# Gumstix.net
KiCad netlist of a schematic drawn in Altium Designer
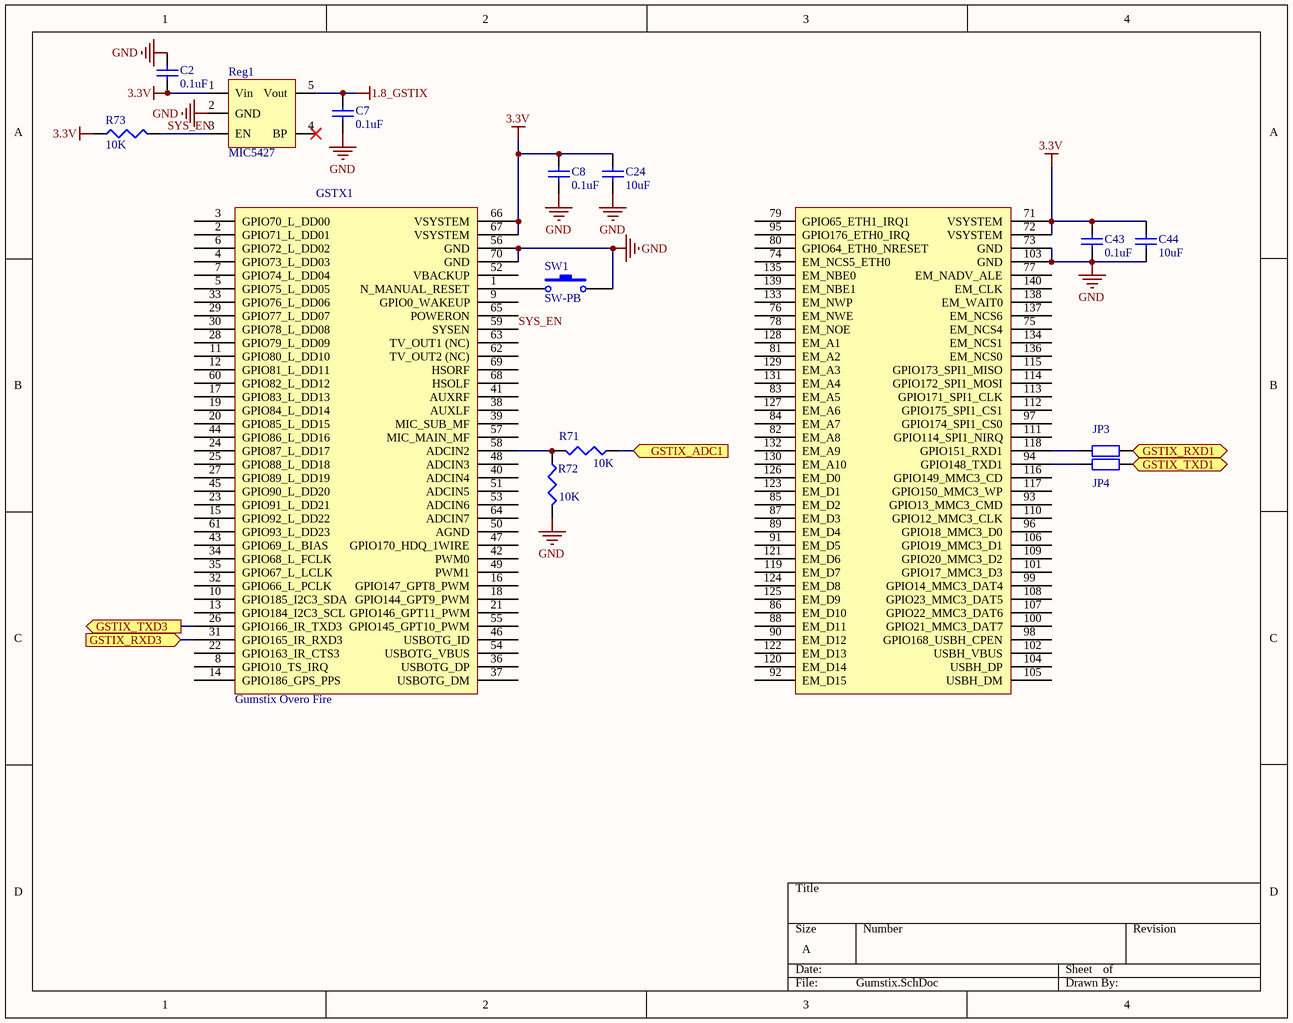
[diagram p0: Gumstix.SchDoc]

(export (version "E")
  (design (tool "Eeschema 10.0.6"))
  (components
    (comp (ref "C2")
      (value "0.1uF")
      (footprint "0603_CAP")
      (description "Capacitor")
      (fields (field (name "Comment") "X7R Cap") (field (name "PUBLISHER") "Altium Limited"))
      (libsource (lib "Miscellaneous Devices") (part "Cap"))
    )
    (comp (ref "C7")
      (value "0.1uF")
      (footprint "0603_CAP")
      (description "Capacitor")
      (fields (field (name "Comment") "X7R Cap") (field (name "PUBLISHER") "Altium Limited"))
      (libsource (lib "Miscellaneous Devices") (part "Cap"))
    )
    (comp (ref "C8")
      (value "0.1uF")
      (footprint "0603_CAP")
      (description "Capacitor")
      (fields (field (name "Comment") "X7R Cap") (field (name "PUBLISHER") "Altium Limited"))
      (libsource (lib "Miscellaneous Devices") (part "Cap"))
    )
    (comp (ref "C24")
      (value "10uF")
      (footprint "0603_CAP")
      (description "Capacitor")
      (fields (field (name "Comment") "X7R Cap") (field (name "PUBLISHER") "Altium Limited"))
      (libsource (lib "Miscellaneous Devices") (part "Cap"))
    )
    (comp (ref "C43")
      (value "0.1uF")
      (footprint "0603_CAP")
      (description "Capacitor")
      (fields (field (name "Comment") "X7R Cap") (field (name "PUBLISHER") "Altium Limited"))
      (libsource (lib "Miscellaneous Devices") (part "Cap"))
    )
    (comp (ref "C44")
      (value "10uF")
      (footprint "0603_CAP")
      (description "Capacitor")
      (fields (field (name "Comment") "X7R Cap") (field (name "PUBLISHER") "Altium Limited"))
      (libsource (lib "Miscellaneous Devices") (part "Cap"))
    )
    (comp (ref "GSTX1")
      (value "Gumstix Overo Fire")
      (footprint "GUMSTIX")
      (libsource (lib "Components") (part "GUMSTIX"))
    )
    (comp (ref "JP3")
      (value "~")
      (footprint "0603_RES")
      (description "Resistor")
      (fields (field (name "PUBLISHER") "Altium Limited"))
      (libsource (lib "Miscellaneous Devices") (part "Res2"))
    )
    (comp (ref "JP4")
      (value "~")
      (footprint "0603_RES")
      (description "Resistor")
      (fields (field (name "PUBLISHER") "Altium Limited"))
      (libsource (lib "Miscellaneous Devices") (part "Res2"))
    )
    (comp (ref "R71")
      (value "10K")
      (footprint "0603_RES")
      (description "Resistor")
      (fields (field (name "Comment") "Rpull") (field (name "PUBLISHER") "Altium Limited"))
      (libsource (lib "Miscellaneous Devices") (part "Res3"))
    )
    (comp (ref "R72")
      (value "10K")
      (footprint "0603_RES")
      (description "Resistor")
      (fields (field (name "Comment") "Rpull") (field (name "PUBLISHER") "Altium Limited"))
      (libsource (lib "Miscellaneous Devices") (part "Res3"))
    )
    (comp (ref "R73")
      (value "10K")
      (footprint "0603_RES")
      (description "Resistor")
      (fields (field (name "Comment") "Rpull") (field (name "PUBLISHER") "Altium Limited"))
      (libsource (lib "Miscellaneous Devices") (part "Res3"))
    )
    (comp (ref "Reg1")
      (value "MIC5427")
      (footprint "SOT23-STD-5-Lead")
      (description "576-1288-1-ND")
      (fields
        (field (name "MANUFACTURER") "Micrel Inc")
        (field (name "MANUFACTURER PART NUMBER") "MIC5247-1.8YM5 TR")
      )
      (libsource (lib "Components") (part "1.8V LDO Regulator"))
    )
    (comp (ref "SW1")
      (value "SW-PB")
      (footprint "SM_SW")
      (description "Switch")
      (fields
        (field (name "MANUFACTURER") "C&K Components")
        (field (name "MANUFACTURER PART NUMBER") "PTS525SK08SMTR LFS")
        (field (name "PUBLISHER") "Altium Limited")
      )
      (libsource (lib "Miscellaneous Devices") (part "SW-PB"))
    )
  )
  (nets
    (net (code "1") (name "/GSTIX_ADC1") (class "Default")
      (node (ref "R71") (pin "1") (pinfunction "1_1") (pintype "passive"))
    )
    (net (code "2") (name "/GSTIX_RXD1") (class "Default")
      (node (ref "JP3") (pin "2") (pinfunction "2_2") (pintype "passive"))
    )
    (net (code "3") (name "/GSTIX_RXD3") (class "Default")
      (node (ref "GSTX1") (pin "31") (pinfunction "GPIO165_IR_RXD3_31") (pintype "passive"))
    )
    (net (code "4") (name "/GSTIX_TXD1") (class "Default")
      (node (ref "JP4") (pin "2") (pinfunction "2_2") (pintype "passive"))
    )
    (net (code "5") (name "/GSTIX_TXD3") (class "Default")
      (node (ref "GSTX1") (pin "26") (pinfunction "GPIO166_IR_TXD3_26") (pintype "passive"))
    )
    (net (code "6") (name "/SYS_EN") (class "Default")
      (node (ref "GSTX1") (pin "59") (pinfunction "SYSEN_59") (pintype "passive"))
      (node (ref "R73") (pin "2") (pinfunction "2_2") (pintype "passive"))
      (node (ref "Reg1") (pin "3") (pinfunction "EN_3") (pintype "passive"))
    )
    (net (code "7") (name "1.8_GSTIX") (class "Default")
      (node (ref "C7") (pin "1") (pinfunction "1_1") (pintype "passive"))
      (node (ref "Reg1") (pin "5") (pinfunction "Vout_5") (pintype "passive"))
    )
    (net (code "8") (name "3.3V") (class "Default")
      (node (ref "C2") (pin "1") (pinfunction "1_1") (pintype "passive"))
      (node (ref "C24") (pin "1") (pinfunction "1_1") (pintype "passive"))
      (node (ref "C43") (pin "1") (pinfunction "1_1") (pintype "passive"))
      (node (ref "C44") (pin "1") (pinfunction "1_1") (pintype "passive"))
      (node (ref "C8") (pin "1") (pinfunction "1_1") (pintype "passive"))
      (node (ref "GSTX1") (pin "66") (pinfunction "VSYSTEM_66") (pintype "passive"))
      (node (ref "GSTX1") (pin "67") (pinfunction "VSYSTEM_67") (pintype "passive"))
      (node (ref "GSTX1") (pin "71") (pinfunction "VSYSTEM_71") (pintype "passive"))
      (node (ref "GSTX1") (pin "72") (pinfunction "VSYSTEM_72") (pintype "passive"))
      (node (ref "R73") (pin "1") (pinfunction "1_1") (pintype "passive"))
      (node (ref "Reg1") (pin "1") (pinfunction "Vin_1") (pintype "passive"))
    )
    (net (code "9") (name "GND") (class "Default")
      (node (ref "C2") (pin "2") (pinfunction "2_2") (pintype "passive"))
      (node (ref "C24") (pin "2") (pinfunction "2_2") (pintype "passive"))
      (node (ref "C43") (pin "2") (pinfunction "2_2") (pintype "passive"))
      (node (ref "C44") (pin "2") (pinfunction "2_2") (pintype "passive"))
      (node (ref "C7") (pin "2") (pinfunction "2_2") (pintype "passive"))
      (node (ref "C8") (pin "2") (pinfunction "2_2") (pintype "passive"))
      (node (ref "GSTX1") (pin "103") (pinfunction "GND_103") (pintype "passive"))
      (node (ref "GSTX1") (pin "56") (pinfunction "GND_56") (pintype "passive"))
      (node (ref "GSTX1") (pin "70") (pinfunction "GND_70") (pintype "passive"))
      (node (ref "GSTX1") (pin "73") (pinfunction "GND_73") (pintype "passive"))
      (node (ref "R72") (pin "2") (pinfunction "2_2") (pintype "passive"))
      (node (ref "Reg1") (pin "2") (pinfunction "GND_2") (pintype "passive"))
      (node (ref "SW1") (pin "2") (pinfunction "2_2") (pintype "passive"))
    )
    (net (code "10") (name "Net-(GSTX1-ADCIN2)") (class "Default")
      (node (ref "GSTX1") (pin "58") (pinfunction "ADCIN2_58") (pintype "passive"))
      (node (ref "R71") (pin "2") (pinfunction "2_2") (pintype "passive"))
      (node (ref "R72") (pin "1") (pinfunction "1_1") (pintype "passive"))
    )
    (net (code "11") (name "Net-(GSTX1-GPIO148_TXD1)") (class "Default")
      (node (ref "GSTX1") (pin "94") (pinfunction "GPIO148_TXD1_94") (pintype "passive"))
      (node (ref "JP4") (pin "1") (pinfunction "1_1") (pintype "passive"))
    )
    (net (code "12") (name "Net-(GSTX1-GPIO151_RXD1)") (class "Default")
      (node (ref "GSTX1") (pin "118") (pinfunction "GPIO151_RXD1_118") (pintype "passive"))
      (node (ref "JP3") (pin "1") (pinfunction "1_1") (pintype "passive"))
    )
    (net (code "13") (name "Net-(GSTX1-N_MANUAL_RESET)") (class "Default")
      (node (ref "GSTX1") (pin "1") (pinfunction "N_MANUAL_RESET_1") (pintype "passive"))
      (node (ref "SW1") (pin "1") (pinfunction "1_1") (pintype "passive"))
    )
    (net (code "14") (name "unconnected-(GSTX1-ADCIN3-Pad48)") (class "Default")
      (node (ref "GSTX1") (pin "48") (pinfunction "ADCIN3_48") (pintype "passive"))
    )
    (net (code "15") (name "unconnected-(GSTX1-ADCIN4-Pad40)") (class "Default")
      (node (ref "GSTX1") (pin "40") (pinfunction "ADCIN4_40") (pintype "passive"))
    )
    (net (code "16") (name "unconnected-(GSTX1-ADCIN5-Pad51)") (class "Default")
      (node (ref "GSTX1") (pin "51") (pinfunction "ADCIN5_51") (pintype "passive"))
    )
    (net (code "17") (name "unconnected-(GSTX1-ADCIN6-Pad53)") (class "Default")
      (node (ref "GSTX1") (pin "53") (pinfunction "ADCIN6_53") (pintype "passive"))
    )
    (net (code "18") (name "unconnected-(GSTX1-ADCIN7-Pad64)") (class "Default")
      (node (ref "GSTX1") (pin "64") (pinfunction "ADCIN7_64") (pintype "passive"))
    )
    (net (code "19") (name "unconnected-(GSTX1-AGND-Pad50)") (class "Default")
      (node (ref "GSTX1") (pin "50") (pinfunction "AGND_50") (pintype "passive"))
    )
    (net (code "20") (name "unconnected-(GSTX1-AUXLF-Pad38)") (class "Default")
      (node (ref "GSTX1") (pin "38") (pinfunction "AUXLF_38") (pintype "passive"))
    )
    (net (code "21") (name "unconnected-(GSTX1-AUXRF-Pad41)") (class "Default")
      (node (ref "GSTX1") (pin "41") (pinfunction "AUXRF_41") (pintype "passive"))
    )
    (net (code "22") (name "unconnected-(GSTX1-EM_A1-Pad128)") (class "Default")
      (node (ref "GSTX1") (pin "128") (pinfunction "EM_A1_128") (pintype "passive"))
    )
    (net (code "23") (name "unconnected-(GSTX1-EM_A2-Pad81)") (class "Default")
      (node (ref "GSTX1") (pin "81") (pinfunction "EM_A2_81") (pintype "passive"))
    )
    (net (code "24") (name "unconnected-(GSTX1-EM_A3-Pad129)") (class "Default")
      (node (ref "GSTX1") (pin "129") (pinfunction "EM_A3_129") (pintype "passive"))
    )
    (net (code "25") (name "unconnected-(GSTX1-EM_A4-Pad131)") (class "Default")
      (node (ref "GSTX1") (pin "131") (pinfunction "EM_A4_131") (pintype "passive"))
    )
    (net (code "26") (name "unconnected-(GSTX1-EM_A5-Pad83)") (class "Default")
      (node (ref "GSTX1") (pin "83") (pinfunction "EM_A5_83") (pintype "passive"))
    )
    (net (code "27") (name "unconnected-(GSTX1-EM_A6-Pad127)") (class "Default")
      (node (ref "GSTX1") (pin "127") (pinfunction "EM_A6_127") (pintype "passive"))
    )
    (net (code "28") (name "unconnected-(GSTX1-EM_A7-Pad84)") (class "Default")
      (node (ref "GSTX1") (pin "84") (pinfunction "EM_A7_84") (pintype "passive"))
    )
    (net (code "29") (name "unconnected-(GSTX1-EM_A8-Pad82)") (class "Default")
      (node (ref "GSTX1") (pin "82") (pinfunction "EM_A8_82") (pintype "passive"))
    )
    (net (code "30") (name "unconnected-(GSTX1-EM_A9-Pad132)") (class "Default")
      (node (ref "GSTX1") (pin "132") (pinfunction "EM_A9_132") (pintype "passive"))
    )
    (net (code "31") (name "unconnected-(GSTX1-EM_A10-Pad130)") (class "Default")
      (node (ref "GSTX1") (pin "130") (pinfunction "EM_A10_130") (pintype "passive"))
    )
    (net (code "32") (name "unconnected-(GSTX1-EM_CLK-Pad140)") (class "Default")
      (node (ref "GSTX1") (pin "140") (pinfunction "EM_CLK_140") (pintype "passive"))
    )
    (net (code "33") (name "unconnected-(GSTX1-EM_D0-Pad126)") (class "Default")
      (node (ref "GSTX1") (pin "126") (pinfunction "EM_D0_126") (pintype "passive"))
    )
    (net (code "34") (name "unconnected-(GSTX1-EM_D1-Pad123)") (class "Default")
      (node (ref "GSTX1") (pin "123") (pinfunction "EM_D1_123") (pintype "passive"))
    )
    (net (code "35") (name "unconnected-(GSTX1-EM_D2-Pad85)") (class "Default")
      (node (ref "GSTX1") (pin "85") (pinfunction "EM_D2_85") (pintype "passive"))
    )
    (net (code "36") (name "unconnected-(GSTX1-EM_D3-Pad87)") (class "Default")
      (node (ref "GSTX1") (pin "87") (pinfunction "EM_D3_87") (pintype "passive"))
    )
    (net (code "37") (name "unconnected-(GSTX1-EM_D4-Pad89)") (class "Default")
      (node (ref "GSTX1") (pin "89") (pinfunction "EM_D4_89") (pintype "passive"))
    )
    (net (code "38") (name "unconnected-(GSTX1-EM_D5-Pad91)") (class "Default")
      (node (ref "GSTX1") (pin "91") (pinfunction "EM_D5_91") (pintype "passive"))
    )
    (net (code "39") (name "unconnected-(GSTX1-EM_D6-Pad121)") (class "Default")
      (node (ref "GSTX1") (pin "121") (pinfunction "EM_D6_121") (pintype "passive"))
    )
    (net (code "40") (name "unconnected-(GSTX1-EM_D7-Pad119)") (class "Default")
      (node (ref "GSTX1") (pin "119") (pinfunction "EM_D7_119") (pintype "passive"))
    )
    (net (code "41") (name "unconnected-(GSTX1-EM_D8-Pad124)") (class "Default")
      (node (ref "GSTX1") (pin "124") (pinfunction "EM_D8_124") (pintype "passive"))
    )
    (net (code "42") (name "unconnected-(GSTX1-EM_D9-Pad125)") (class "Default")
      (node (ref "GSTX1") (pin "125") (pinfunction "EM_D9_125") (pintype "passive"))
    )
    (net (code "43") (name "unconnected-(GSTX1-EM_D10-Pad86)") (class "Default")
      (node (ref "GSTX1") (pin "86") (pinfunction "EM_D10_86") (pintype "passive"))
    )
    (net (code "44") (name "unconnected-(GSTX1-EM_D11-Pad88)") (class "Default")
      (node (ref "GSTX1") (pin "88") (pinfunction "EM_D11_88") (pintype "passive"))
    )
    (net (code "45") (name "unconnected-(GSTX1-EM_D12-Pad90)") (class "Default")
      (node (ref "GSTX1") (pin "90") (pinfunction "EM_D12_90") (pintype "passive"))
    )
    (net (code "46") (name "unconnected-(GSTX1-EM_D13-Pad122)") (class "Default")
      (node (ref "GSTX1") (pin "122") (pinfunction "EM_D13_122") (pintype "passive"))
    )
    (net (code "47") (name "unconnected-(GSTX1-EM_D14-Pad120)") (class "Default")
      (node (ref "GSTX1") (pin "120") (pinfunction "EM_D14_120") (pintype "passive"))
    )
    (net (code "48") (name "unconnected-(GSTX1-EM_D15-Pad92)") (class "Default")
      (node (ref "GSTX1") (pin "92") (pinfunction "EM_D15_92") (pintype "passive"))
    )
    (net (code "49") (name "unconnected-(GSTX1-EM_NADV_ALE-Pad77)") (class "Default")
      (node (ref "GSTX1") (pin "77") (pinfunction "EM_NADV_ALE_77") (pintype "passive"))
    )
    (net (code "50") (name "unconnected-(GSTX1-EM_NBE0-Pad135)") (class "Default")
      (node (ref "GSTX1") (pin "135") (pinfunction "EM_NBE0_135") (pintype "passive"))
    )
    (net (code "51") (name "unconnected-(GSTX1-EM_NBE1-Pad139)") (class "Default")
      (node (ref "GSTX1") (pin "139") (pinfunction "EM_NBE1_139") (pintype "passive"))
    )
    (net (code "52") (name "unconnected-(GSTX1-EM_NCS0-Pad136)") (class "Default")
      (node (ref "GSTX1") (pin "136") (pinfunction "EM_NCS0_136") (pintype "passive"))
    )
    (net (code "53") (name "unconnected-(GSTX1-EM_NCS1-Pad134)") (class "Default")
      (node (ref "GSTX1") (pin "134") (pinfunction "EM_NCS1_134") (pintype "passive"))
    )
    (net (code "54") (name "unconnected-(GSTX1-EM_NCS4-Pad75)") (class "Default")
      (node (ref "GSTX1") (pin "75") (pinfunction "EM_NCS4_75") (pintype "passive"))
    )
    (net (code "55") (name "unconnected-(GSTX1-EM_NCS5_ETH0-Pad74)") (class "Default")
      (node (ref "GSTX1") (pin "74") (pinfunction "EM_NCS5_ETH0_74") (pintype "passive"))
    )
    (net (code "56") (name "unconnected-(GSTX1-EM_NCS6-Pad137)") (class "Default")
      (node (ref "GSTX1") (pin "137") (pinfunction "EM_NCS6_137") (pintype "passive"))
    )
    (net (code "57") (name "unconnected-(GSTX1-EM_NOE-Pad78)") (class "Default")
      (node (ref "GSTX1") (pin "78") (pinfunction "EM_NOE_78") (pintype "passive"))
    )
    (net (code "58") (name "unconnected-(GSTX1-EM_NWE-Pad76)") (class "Default")
      (node (ref "GSTX1") (pin "76") (pinfunction "EM_NWE_76") (pintype "passive"))
    )
    (net (code "59") (name "unconnected-(GSTX1-EM_NWP-Pad133)") (class "Default")
      (node (ref "GSTX1") (pin "133") (pinfunction "EM_NWP_133") (pintype "passive"))
    )
    (net (code "60") (name "unconnected-(GSTX1-EM_WAIT0-Pad138)") (class "Default")
      (node (ref "GSTX1") (pin "138") (pinfunction "EM_WAIT0_138") (pintype "passive"))
    )
    (net (code "61") (name "unconnected-(GSTX1-GPIO0_WAKEUP-Pad9)") (class "Default")
      (node (ref "GSTX1") (pin "9") (pinfunction "GPIO0_WAKEUP_9") (pintype "passive"))
    )
    (net (code "62") (name "unconnected-(GSTX1-GPIO10_TS_IRQ-Pad8)") (class "Default")
      (node (ref "GSTX1") (pin "8") (pinfunction "GPIO10_TS_IRQ_8") (pintype "passive"))
    )
    (net (code "63") (name "unconnected-(GSTX1-GPIO12_MMC3_CLK-Pad110)") (class "Default")
      (node (ref "GSTX1") (pin "110") (pinfunction "GPIO12_MMC3_CLK_110") (pintype "passive"))
    )
    (net (code "64") (name "unconnected-(GSTX1-GPIO13_MMC3_CMD-Pad93)") (class "Default")
      (node (ref "GSTX1") (pin "93") (pinfunction "GPIO13_MMC3_CMD_93") (pintype "passive"))
    )
    (net (code "65") (name "unconnected-(GSTX1-GPIO14_MMC3_DAT4-Pad99)") (class "Default")
      (node (ref "GSTX1") (pin "99") (pinfunction "GPIO14_MMC3_DAT4_99") (pintype "passive"))
    )
    (net (code "66") (name "unconnected-(GSTX1-GPIO17_MMC3_D3-Pad101)") (class "Default")
      (node (ref "GSTX1") (pin "101") (pinfunction "GPIO17_MMC3_D3_101") (pintype "passive"))
    )
    (net (code "67") (name "unconnected-(GSTX1-GPIO18_MMC3_D0-Pad96)") (class "Default")
      (node (ref "GSTX1") (pin "96") (pinfunction "GPIO18_MMC3_D0_96") (pintype "passive"))
    )
    (net (code "68") (name "unconnected-(GSTX1-GPIO19_MMC3_D1-Pad106)") (class "Default")
      (node (ref "GSTX1") (pin "106") (pinfunction "GPIO19_MMC3_D1_106") (pintype "passive"))
    )
    (net (code "69") (name "unconnected-(GSTX1-GPIO20_MMC3_D2-Pad109)") (class "Default")
      (node (ref "GSTX1") (pin "109") (pinfunction "GPIO20_MMC3_D2_109") (pintype "passive"))
    )
    (net (code "70") (name "unconnected-(GSTX1-GPIO21_MMC3_DAT7-Pad100)") (class "Default")
      (node (ref "GSTX1") (pin "100") (pinfunction "GPIO21_MMC3_DAT7_100") (pintype "passive"))
    )
    (net (code "71") (name "unconnected-(GSTX1-GPIO22_MMC3_DAT6-Pad107)") (class "Default")
      (node (ref "GSTX1") (pin "107") (pinfunction "GPIO22_MMC3_DAT6_107") (pintype "passive"))
    )
    (net (code "72") (name "unconnected-(GSTX1-GPIO23_MMC3_DAT5-Pad108)") (class "Default")
      (node (ref "GSTX1") (pin "108") (pinfunction "GPIO23_MMC3_DAT5_108") (pintype "passive"))
    )
    (net (code "73") (name "unconnected-(GSTX1-GPIO64_ETH0_NRESET-Pad80)") (class "Default")
      (node (ref "GSTX1") (pin "80") (pinfunction "GPIO64_ETH0_NRESET_80") (pintype "passive"))
    )
    (net (code "74") (name "unconnected-(GSTX1-GPIO65_ETH1_IRQ1-Pad79)") (class "Default")
      (node (ref "GSTX1") (pin "79") (pinfunction "GPIO65_ETH1_IRQ1_79") (pintype "passive"))
    )
    (net (code "75") (name "unconnected-(GSTX1-GPIO66_L_PCLK-Pad32)") (class "Default")
      (node (ref "GSTX1") (pin "32") (pinfunction "GPIO66_L_PCLK_32") (pintype "passive"))
    )
    (net (code "76") (name "unconnected-(GSTX1-GPIO67_L_LCLK-Pad35)") (class "Default")
      (node (ref "GSTX1") (pin "35") (pinfunction "GPIO67_L_LCLK_35") (pintype "passive"))
    )
    (net (code "77") (name "unconnected-(GSTX1-GPIO68_L_FCLK-Pad34)") (class "Default")
      (node (ref "GSTX1") (pin "34") (pinfunction "GPIO68_L_FCLK_34") (pintype "passive"))
    )
    (net (code "78") (name "unconnected-(GSTX1-GPIO69_L_BIAS-Pad43)") (class "Default")
      (node (ref "GSTX1") (pin "43") (pinfunction "GPIO69_L_BIAS_43") (pintype "passive"))
    )
    (net (code "79") (name "unconnected-(GSTX1-GPIO70_L_DD00-Pad3)") (class "Default")
      (node (ref "GSTX1") (pin "3") (pinfunction "GPIO70_L_DD00_3") (pintype "passive"))
    )
    (net (code "80") (name "unconnected-(GSTX1-GPIO71_L_DD01-Pad2)") (class "Default")
      (node (ref "GSTX1") (pin "2") (pinfunction "GPIO71_L_DD01_2") (pintype "passive"))
    )
    (net (code "81") (name "unconnected-(GSTX1-GPIO72_L_DD02-Pad6)") (class "Default")
      (node (ref "GSTX1") (pin "6") (pinfunction "GPIO72_L_DD02_6") (pintype "passive"))
    )
    (net (code "82") (name "unconnected-(GSTX1-GPIO73_L_DD03-Pad4)") (class "Default")
      (node (ref "GSTX1") (pin "4") (pinfunction "GPIO73_L_DD03_4") (pintype "passive"))
    )
    (net (code "83") (name "unconnected-(GSTX1-GPIO74_L_DD04-Pad7)") (class "Default")
      (node (ref "GSTX1") (pin "7") (pinfunction "GPIO74_L_DD04_7") (pintype "passive"))
    )
    (net (code "84") (name "unconnected-(GSTX1-GPIO75_L_DD05-Pad5)") (class "Default")
      (node (ref "GSTX1") (pin "5") (pinfunction "GPIO75_L_DD05_5") (pintype "passive"))
    )
    (net (code "85") (name "unconnected-(GSTX1-GPIO76_L_DD06-Pad33)") (class "Default")
      (node (ref "GSTX1") (pin "33") (pinfunction "GPIO76_L_DD06_33") (pintype "passive"))
    )
    (net (code "86") (name "unconnected-(GSTX1-GPIO77_L_DD07-Pad29)") (class "Default")
      (node (ref "GSTX1") (pin "29") (pinfunction "GPIO77_L_DD07_29") (pintype "passive"))
    )
    (net (code "87") (name "unconnected-(GSTX1-GPIO78_L_DD08-Pad30)") (class "Default")
      (node (ref "GSTX1") (pin "30") (pinfunction "GPIO78_L_DD08_30") (pintype "passive"))
    )
    (net (code "88") (name "unconnected-(GSTX1-GPIO79_L_DD09-Pad28)") (class "Default")
      (node (ref "GSTX1") (pin "28") (pinfunction "GPIO79_L_DD09_28") (pintype "passive"))
    )
    (net (code "89") (name "unconnected-(GSTX1-GPIO80_L_DD10-Pad11)") (class "Default")
      (node (ref "GSTX1") (pin "11") (pinfunction "GPIO80_L_DD10_11") (pintype "passive"))
    )
    (net (code "90") (name "unconnected-(GSTX1-GPIO81_L_DD11-Pad12)") (class "Default")
      (node (ref "GSTX1") (pin "12") (pinfunction "GPIO81_L_DD11_12") (pintype "passive"))
    )
    (net (code "91") (name "unconnected-(GSTX1-GPIO82_L_DD12-Pad60)") (class "Default")
      (node (ref "GSTX1") (pin "60") (pinfunction "GPIO82_L_DD12_60") (pintype "passive"))
    )
    (net (code "92") (name "unconnected-(GSTX1-GPIO83_L_DD13-Pad17)") (class "Default")
      (node (ref "GSTX1") (pin "17") (pinfunction "GPIO83_L_DD13_17") (pintype "passive"))
    )
    (net (code "93") (name "unconnected-(GSTX1-GPIO84_L_DD14-Pad19)") (class "Default")
      (node (ref "GSTX1") (pin "19") (pinfunction "GPIO84_L_DD14_19") (pintype "passive"))
    )
    (net (code "94") (name "unconnected-(GSTX1-GPIO85_L_DD15-Pad20)") (class "Default")
      (node (ref "GSTX1") (pin "20") (pinfunction "GPIO85_L_DD15_20") (pintype "passive"))
    )
    (net (code "95") (name "unconnected-(GSTX1-GPIO86_L_DD16-Pad44)") (class "Default")
      (node (ref "GSTX1") (pin "44") (pinfunction "GPIO86_L_DD16_44") (pintype "passive"))
    )
    (net (code "96") (name "unconnected-(GSTX1-GPIO87_L_DD17-Pad24)") (class "Default")
      (node (ref "GSTX1") (pin "24") (pinfunction "GPIO87_L_DD17_24") (pintype "passive"))
    )
    (net (code "97") (name "unconnected-(GSTX1-GPIO88_L_DD18-Pad25)") (class "Default")
      (node (ref "GSTX1") (pin "25") (pinfunction "GPIO88_L_DD18_25") (pintype "passive"))
    )
    (net (code "98") (name "unconnected-(GSTX1-GPIO89_L_DD19-Pad27)") (class "Default")
      (node (ref "GSTX1") (pin "27") (pinfunction "GPIO89_L_DD19_27") (pintype "passive"))
    )
    (net (code "99") (name "unconnected-(GSTX1-GPIO90_L_DD20-Pad45)") (class "Default")
      (node (ref "GSTX1") (pin "45") (pinfunction "GPIO90_L_DD20_45") (pintype "passive"))
    )
    (net (code "100") (name "unconnected-(GSTX1-GPIO91_L_DD21-Pad23)") (class "Default")
      (node (ref "GSTX1") (pin "23") (pinfunction "GPIO91_L_DD21_23") (pintype "passive"))
    )
    (net (code "101") (name "unconnected-(GSTX1-GPIO92_L_DD22-Pad15)") (class "Default")
      (node (ref "GSTX1") (pin "15") (pinfunction "GPIO92_L_DD22_15") (pintype "passive"))
    )
    (net (code "102") (name "unconnected-(GSTX1-GPIO93_L_DD23-Pad61)") (class "Default")
      (node (ref "GSTX1") (pin "61") (pinfunction "GPIO93_L_DD23_61") (pintype "passive"))
    )
    (net (code "103") (name "unconnected-(GSTX1-GPIO114_SPI1_NIRQ-Pad111)") (class "Default")
      (node (ref "GSTX1") (pin "111") (pinfunction "GPIO114_SPI1_NIRQ_111") (pintype "passive"))
    )
    (net (code "104") (name "unconnected-(GSTX1-GPIO144_GPT9_PWM-Pad18)") (class "Default")
      (node (ref "GSTX1") (pin "18") (pinfunction "GPIO144_GPT9_PWM_18") (pintype "passive"))
    )
    (net (code "105") (name "unconnected-(GSTX1-GPIO145_GPT10_PWM-Pad55)") (class "Default")
      (node (ref "GSTX1") (pin "55") (pinfunction "GPIO145_GPT10_PWM_55") (pintype "passive"))
    )
    (net (code "106") (name "unconnected-(GSTX1-GPIO146_GPT11_PWM-Pad21)") (class "Default")
      (node (ref "GSTX1") (pin "21") (pinfunction "GPIO146_GPT11_PWM_21") (pintype "passive"))
    )
    (net (code "107") (name "unconnected-(GSTX1-GPIO147_GPT8_PWM-Pad16)") (class "Default")
      (node (ref "GSTX1") (pin "16") (pinfunction "GPIO147_GPT8_PWM_16") (pintype "passive"))
    )
    (net (code "108") (name "unconnected-(GSTX1-GPIO149_MMC3_CD-Pad116)") (class "Default")
      (node (ref "GSTX1") (pin "116") (pinfunction "GPIO149_MMC3_CD_116") (pintype "passive"))
    )
    (net (code "109") (name "unconnected-(GSTX1-GPIO150_MMC3_WP-Pad117)") (class "Default")
      (node (ref "GSTX1") (pin "117") (pinfunction "GPIO150_MMC3_WP_117") (pintype "passive"))
    )
    (net (code "110") (name "unconnected-(GSTX1-GPIO163_IR_CTS3-Pad22)") (class "Default")
      (node (ref "GSTX1") (pin "22") (pinfunction "GPIO163_IR_CTS3_22") (pintype "passive"))
    )
    (net (code "111") (name "unconnected-(GSTX1-GPIO168_USBH_CPEN-Pad98)") (class "Default")
      (node (ref "GSTX1") (pin "98") (pinfunction "GPIO168_USBH_CPEN_98") (pintype "passive"))
    )
    (net (code "112") (name "unconnected-(GSTX1-GPIO170_HDQ_1WIRE-Pad47)") (class "Default")
      (node (ref "GSTX1") (pin "47") (pinfunction "GPIO170_HDQ_1WIRE_47") (pintype "passive"))
    )
    (net (code "113") (name "unconnected-(GSTX1-GPIO171_SPI1_CLK-Pad113)") (class "Default")
      (node (ref "GSTX1") (pin "113") (pinfunction "GPIO171_SPI1_CLK_113") (pintype "passive"))
    )
    (net (code "114") (name "unconnected-(GSTX1-GPIO172_SPI1_MOSI-Pad114)") (class "Default")
      (node (ref "GSTX1") (pin "114") (pinfunction "GPIO172_SPI1_MOSI_114") (pintype "passive"))
    )
    (net (code "115") (name "unconnected-(GSTX1-GPIO173_SPI1_MISO-Pad115)") (class "Default")
      (node (ref "GSTX1") (pin "115") (pinfunction "GPIO173_SPI1_MISO_115") (pintype "passive"))
    )
    (net (code "116") (name "unconnected-(GSTX1-GPIO174_SPI1_CS0-Pad97)") (class "Default")
      (node (ref "GSTX1") (pin "97") (pinfunction "GPIO174_SPI1_CS0_97") (pintype "passive"))
    )
    (net (code "117") (name "unconnected-(GSTX1-GPIO175_SPI1_CS1-Pad112)") (class "Default")
      (node (ref "GSTX1") (pin "112") (pinfunction "GPIO175_SPI1_CS1_112") (pintype "passive"))
    )
    (net (code "118") (name "unconnected-(GSTX1-GPIO176_ETH0_IRQ-Pad95)") (class "Default")
      (node (ref "GSTX1") (pin "95") (pinfunction "GPIO176_ETH0_IRQ_95") (pintype "passive"))
    )
    (net (code "119") (name "unconnected-(GSTX1-GPIO184_I2C3_SCL-Pad13)") (class "Default")
      (node (ref "GSTX1") (pin "13") (pinfunction "GPIO184_I2C3_SCL_13") (pintype "passive"))
    )
    (net (code "120") (name "unconnected-(GSTX1-GPIO185_I2C3_SDA-Pad10)") (class "Default")
      (node (ref "GSTX1") (pin "10") (pinfunction "GPIO185_I2C3_SDA_10") (pintype "passive"))
    )
    (net (code "121") (name "unconnected-(GSTX1-GPIO186_GPS_PPS-Pad14)") (class "Default")
      (node (ref "GSTX1") (pin "14") (pinfunction "GPIO186_GPS_PPS_14") (pintype "passive"))
    )
    (net (code "122") (name "unconnected-(GSTX1-HSOLF-Pad68)") (class "Default")
      (node (ref "GSTX1") (pin "68") (pinfunction "HSOLF_68") (pintype "passive"))
    )
    (net (code "123") (name "unconnected-(GSTX1-HSORF-Pad69)") (class "Default")
      (node (ref "GSTX1") (pin "69") (pinfunction "HSORF_69") (pintype "passive"))
    )
    (net (code "124") (name "unconnected-(GSTX1-MIC_MAIN_MF-Pad57)") (class "Default")
      (node (ref "GSTX1") (pin "57") (pinfunction "MIC_MAIN_MF_57") (pintype "passive"))
    )
    (net (code "125") (name "unconnected-(GSTX1-MIC_SUB_MF-Pad39)") (class "Default")
      (node (ref "GSTX1") (pin "39") (pinfunction "MIC_SUB_MF_39") (pintype "passive"))
    )
    (net (code "126") (name "unconnected-(GSTX1-POWERON-Pad65)") (class "Default")
      (node (ref "GSTX1") (pin "65") (pinfunction "POWERON_65") (pintype "passive"))
    )
    (net (code "127") (name "unconnected-(GSTX1-PWM0-Pad42)") (class "Default")
      (node (ref "GSTX1") (pin "42") (pinfunction "PWM0_42") (pintype "passive"))
    )
    (net (code "128") (name "unconnected-(GSTX1-PWM1-Pad49)") (class "Default")
      (node (ref "GSTX1") (pin "49") (pinfunction "PWM1_49") (pintype "passive"))
    )
    (net (code "129") (name "unconnected-(GSTX1-TV_OUT1_(NC)-Pad63)") (class "Default")
      (node (ref "GSTX1") (pin "63") (pinfunction "TV_OUT1_(NC)_63") (pintype "passive"))
    )
    (net (code "130") (name "unconnected-(GSTX1-TV_OUT2_(NC)-Pad62)") (class "Default")
      (node (ref "GSTX1") (pin "62") (pinfunction "TV_OUT2_(NC)_62") (pintype "passive"))
    )
    (net (code "131") (name "unconnected-(GSTX1-USBH_DM-Pad105)") (class "Default")
      (node (ref "GSTX1") (pin "105") (pinfunction "USBH_DM_105") (pintype "passive"))
    )
    (net (code "132") (name "unconnected-(GSTX1-USBH_DP-Pad104)") (class "Default")
      (node (ref "GSTX1") (pin "104") (pinfunction "USBH_DP_104") (pintype "passive"))
    )
    (net (code "133") (name "unconnected-(GSTX1-USBH_VBUS-Pad102)") (class "Default")
      (node (ref "GSTX1") (pin "102") (pinfunction "USBH_VBUS_102") (pintype "passive"))
    )
    (net (code "134") (name "unconnected-(GSTX1-USBOTG_DM-Pad37)") (class "Default")
      (node (ref "GSTX1") (pin "37") (pinfunction "USBOTG_DM_37") (pintype "passive"))
    )
    (net (code "135") (name "unconnected-(GSTX1-USBOTG_DP-Pad36)") (class "Default")
      (node (ref "GSTX1") (pin "36") (pinfunction "USBOTG_DP_36") (pintype "passive"))
    )
    (net (code "136") (name "unconnected-(GSTX1-USBOTG_ID-Pad46)") (class "Default")
      (node (ref "GSTX1") (pin "46") (pinfunction "USBOTG_ID_46") (pintype "passive"))
    )
    (net (code "137") (name "unconnected-(GSTX1-USBOTG_VBUS-Pad54)") (class "Default")
      (node (ref "GSTX1") (pin "54") (pinfunction "USBOTG_VBUS_54") (pintype "passive"))
    )
    (net (code "138") (name "unconnected-(GSTX1-VBACKUP-Pad52)") (class "Default")
      (node (ref "GSTX1") (pin "52") (pinfunction "VBACKUP_52") (pintype "passive"))
    )
    (net (code "139") (name "unconnected-(Reg1-BP-Pad4)") (class "Default")
      (node (ref "Reg1") (pin "4") (pinfunction "BP_4") (pintype "passive+no_connect"))
    )
  )
)
